# Thermosistor1.net
KiCad netlist of a schematic drawn in Altium Designer
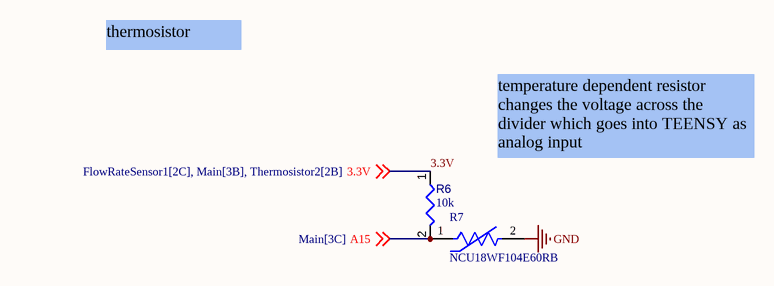
[diagram p0: Thermosistor1.SchDoc]

(export (version "E")
  (design (tool "Eeschema 10.0.6"))
  (components
    (comp (ref "R6")
      (value "10k")
      (footprint "RESC0402(1005)_L")
      (description "Chip Resistor, 10 kOhms, +/-1 %, 63 mW, -55 to 125 degC, 0402")
      (fields (field (name "POWER") "63mW") (field (name "TOLERANCE") "1%"))
      (libsource (lib "Alt_ium Course") (part "RES-2"))
    )
    (comp (ref "R7")
      (value "NCU18WF104E60RB")
      (footprint "FP-NCU18-0_15-IPC_C")
      (description "THERMISTOR NTC")
      (libsource (lib "Altium Content Vault") (part "3b148a6ebabc5fb4d708a66c052d352"))
    )
  )
  (nets
    (net (code "1") (name "3.3V") (class "Default")
      (node (ref "R6") (pin "1") (pinfunction "1_1") (pintype "passive"))
    )
    (net (code "2") (name "A15") (class "Default")
      (node (ref "R6") (pin "2") (pinfunction "2_2") (pintype "passive"))
      (node (ref "R7") (pin "1") (pinfunction "1_1") (pintype "passive"))
    )
    (net (code "3") (name "GND") (class "Default")
      (node (ref "R7") (pin "2") (pinfunction "2_2") (pintype "passive"))
    )
  )
)
